# ProjectAir_Sch.net
KiCad netlist of a schematic drawn in Altium Designer
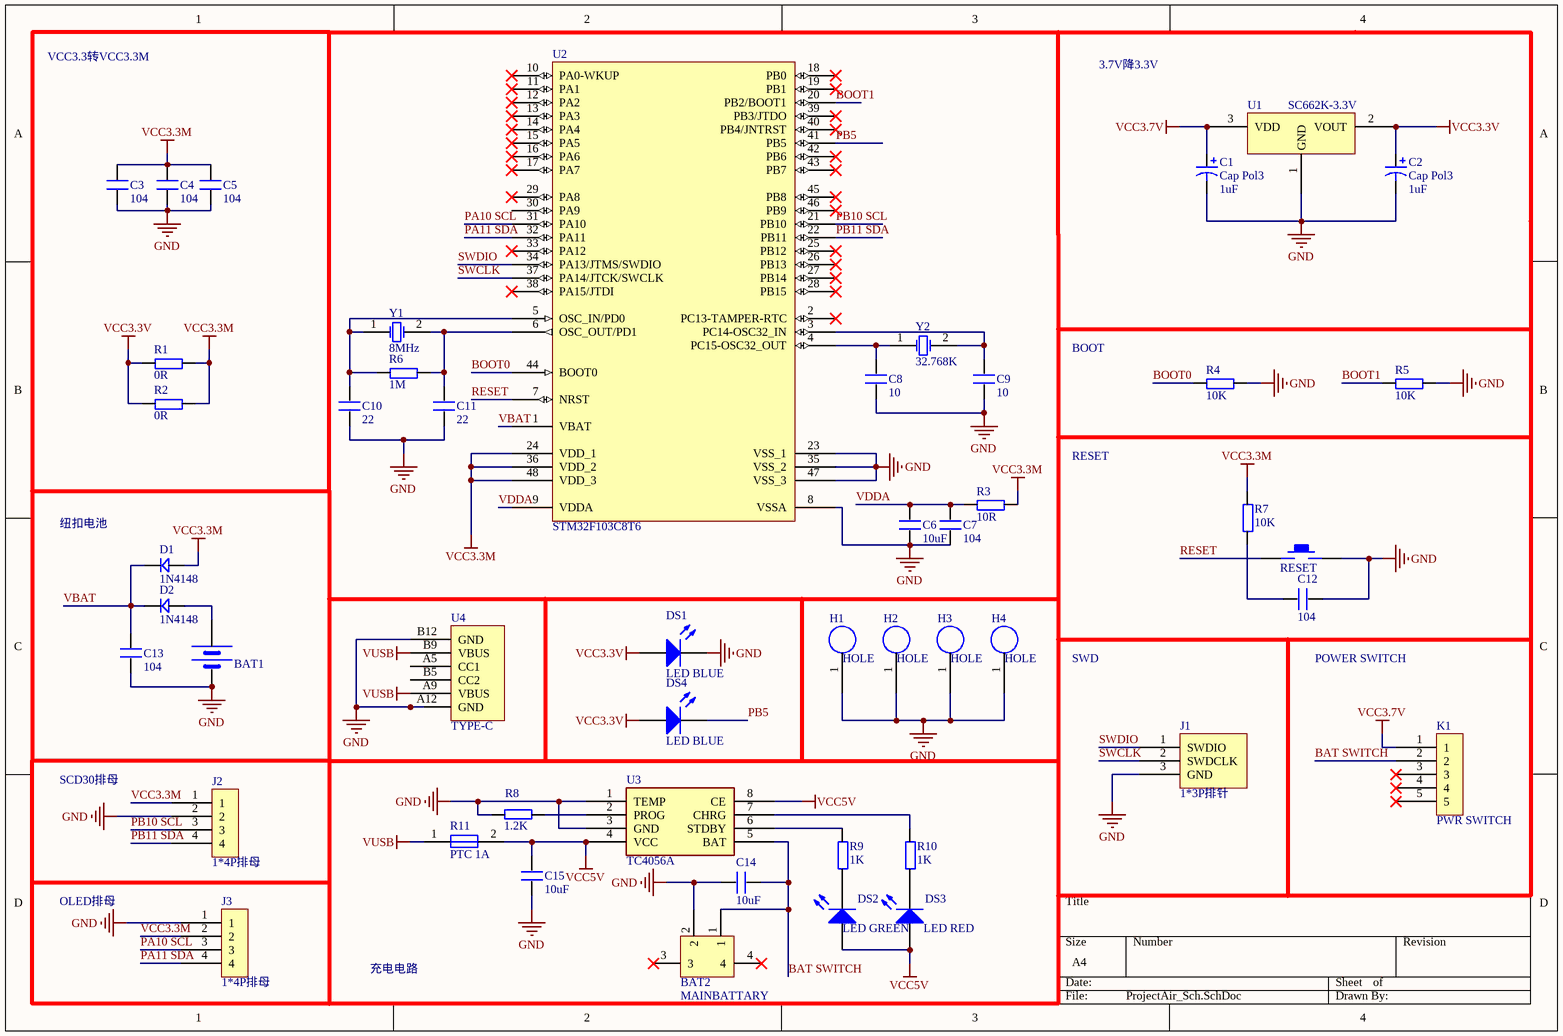
[diagram p0: ProjectAir_Sch.SchDoc]

(export (version "E")
  (design (tool "Eeschema 10.0.6"))
  (components
    (comp (ref "BAT1") (value "BATT") (footprint "BAT_RTC") (libsource (lib "EliteSTM32封装库") (part "BAT")))
    (comp (ref "BAT2")
      (value "MAINBATTARY")
      (footprint "MAINBAT")
      (libsource (lib "ProjectAir_SchLib") (part "MAINBAT"))
    )
    (comp (ref "C1")
      (value "Cap Pol3")
      (footprint "C Pol")
      (description "Polarized Capacitor (Surface Mount)")
      (fields (field (name "ALTIUM_VALUE") "1uF") (field (name "PUBLISHER") "Altium Limited"))
      (libsource (lib "Miscellaneous Devices") (part "Cap Pol3"))
    )
    (comp (ref "C2")
      (value "Cap Pol3")
      (footprint "C Pol")
      (description "Polarized Capacitor (Surface Mount)")
      (fields (field (name "ALTIUM_VALUE") "1uF") (field (name "PUBLISHER") "Altium Limited"))
      (libsource (lib "Miscellaneous Devices") (part "Cap Pol3"))
    )
    (comp (ref "C3") (value "104") (footprint "0805") (libsource (lib "EliteSTM32封装库") (part "C")))
    (comp (ref "C4") (value "104") (footprint "0805") (libsource (lib "EliteSTM32封装库") (part "C")))
    (comp (ref "C5") (value "104") (footprint "0805") (libsource (lib "EliteSTM32封装库") (part "C")))
    (comp (ref "C6") (value "10uF") (footprint "0805") (libsource (lib "EliteSTM32封装库") (part "C")))
    (comp (ref "C7") (value "104") (footprint "0805") (libsource (lib "EliteSTM32封装库") (part "C")))
    (comp (ref "C8") (value "10") (footprint "0805") (libsource (lib "EliteSTM32封装库") (part "C")))
    (comp (ref "C9") (value "10") (footprint "0805") (libsource (lib "EliteSTM32封装库") (part "C")))
    (comp (ref "C10") (value "22") (footprint "0805") (libsource (lib "EliteSTM32封装库") (part "C")))
    (comp (ref "C11") (value "22") (footprint "0805") (libsource (lib "EliteSTM32封装库") (part "C")))
    (comp (ref "C12") (value "104") (footprint "0805") (libsource (lib "EliteSTM32封装库") (part "C")))
    (comp (ref "C13") (value "104") (footprint "0805") (libsource (lib "EliteSTM32封装库") (part "C")))
    (comp (ref "C14") (value "10uF") (footprint "0805") (libsource (lib "EliteSTM32封装库") (part "C_2")))
    (comp (ref "C15") (value "10uF") (footprint "0805") (libsource (lib "EliteSTM32封装库") (part "C_2")))
    (comp (ref "D1") (value "1N4148") (footprint "SOD-123") (libsource (lib "EliteSTM32封装库") (part "D")))
    (comp (ref "D2") (value "1N4148") (footprint "SOD-123") (libsource (lib "EliteSTM32封装库") (part "D")))
    (comp (ref "DS1")
      (value "LED BLUE")
      (footprint "0805D")
      (description "Typical RED, GREEN, YELLOW, AMBER GaAs LED")
      (fields (field (name "PUBLISHER") "Altium Limited"))
      (libsource (lib "EliteSTM32封装库") (part "LED2"))
    )
    (comp (ref "DS2")
      (value "LED GREEN")
      (footprint "0805D")
      (description "Typical RED, GREEN, YELLOW, AMBER GaAs LED")
      (fields (field (name "PUBLISHER") "Altium Limited"))
      (libsource (lib "EliteSTM32封装库") (part "LED2"))
    )
    (comp (ref "DS3")
      (value "LED RED")
      (footprint "0805D")
      (description "Typical RED, GREEN, YELLOW, AMBER GaAs LED")
      (fields (field (name "PUBLISHER") "Altium Limited"))
      (libsource (lib "EliteSTM32封装库") (part "LED2"))
    )
    (comp (ref "DS4")
      (value "LED BLUE")
      (footprint "0805D")
      (description "Typical RED, GREEN, YELLOW, AMBER GaAs LED")
      (fields (field (name "PUBLISHER") "Altium Limited"))
      (libsource (lib "EliteSTM32封装库") (part "LED2"))
    )
    (comp (ref "H1")
      (value "HOLE")
      (footprint "M2孔")
      (description "M2孔")
      (libsource (lib "altium-import") (part "root_1_M2孔_"))
    )
    (comp (ref "H2")
      (value "HOLE")
      (footprint "M2孔")
      (description "M2孔")
      (libsource (lib "altium-import") (part "root_1_M2孔_"))
    )
    (comp (ref "H3")
      (value "HOLE")
      (footprint "M2孔")
      (description "M2孔")
      (libsource (lib "altium-import") (part "root_1_M2孔_"))
    )
    (comp (ref "H4")
      (value "HOLE")
      (footprint "M2孔")
      (description "M2孔")
      (libsource (lib "altium-import") (part "root_1_M2孔_"))
    )
    (comp (ref "J1")
      (value "1*3P排针")
      (footprint "1*3Pin")
      (libsource (lib "altium-import") (part "root_0_1*3P排针_"))
    )
    (comp (ref "J2")
      (value "1*4P排母")
      (footprint "1*4Pin")
      (description "排母")
      (libsource (lib "ProjectAir_SchLib") (part "1*4P排母"))
    )
    (comp (ref "J3")
      (value "1*4P排母")
      (footprint "1*4Pin")
      (description "排母")
      (libsource (lib "ProjectAir_SchLib") (part "1*4P排母"))
    )
    (comp (ref "K1")
      (value "PWR SWITCH")
      (footprint "PWR SWITCH")
      (libsource (lib "altium-import") (part "root_0_PWR SWITCH_"))
    )
    (comp (ref "R1") (value "0R") (footprint "0805R") (libsource (lib "EliteSTM32封装库") (part "R")))
    (comp (ref "R2") (value "0R") (footprint "0805R") (libsource (lib "EliteSTM32封装库") (part "R")))
    (comp (ref "R3") (value "10R") (footprint "0805R") (libsource (lib "EliteSTM32封装库") (part "R")))
    (comp (ref "R4") (value "10K") (footprint "0805R") (libsource (lib "EliteSTM32封装库") (part "R")))
    (comp (ref "R5") (value "10K") (footprint "0805R") (libsource (lib "EliteSTM32封装库") (part "R")))
    (comp (ref "R6") (value "1M") (footprint "0805R") (libsource (lib "EliteSTM32封装库") (part "R")))
    (comp (ref "R7") (value "10K") (footprint "0805R") (libsource (lib "EliteSTM32封装库") (part "R")))
    (comp (ref "R8") (value "1.2K") (footprint "0805R") (libsource (lib "EliteSTM32封装库") (part "R_1")))
    (comp (ref "R9") (value "1K") (footprint "0805R") (libsource (lib "EliteSTM32封装库") (part "R_1")))
    (comp (ref "R10") (value "1K") (footprint "0805R") (libsource (lib "EliteSTM32封装库") (part "R_1")))
    (comp (ref "R11")
      (value "PTC 1A")
      (footprint "PTC")
      (libsource (lib "altium-import") (part "root_0_PTC保险_"))
    )
    (comp (ref "RESET") (value "KEY_M") (footprint "SMD") (libsource (lib "EliteSTM32封装库") (part "KEY_M")))
    (comp (ref "U1")
      (value "SC662K-3.3V")
      (footprint "SOT23-3")
      (description "SCK662K-3.3V")
      (libsource (lib "ProjectAir_SchLib") (part "SC662K-3.3V"))
    )
    (comp (ref "U2")
      (value "STM32F103C8T6")
      (footprint "STM32F103C8T6")
      (description "STM32 ARM-based 32-bit MCU with 64 Kbytes Flash, 48-pin LQFP, Industrial Temperature")
      (fields (field (name "PUBLISHER") "Altium Limited"))
      (libsource (lib "ST Microcontroller 32-Bit STM32") (part "STM32F103C8T6"))
    )
    (comp (ref "U3")
      (value "TC4056A")
      (footprint "ESOP-8")
      (description "充电芯片")
      (libsource (lib "ProjectAir_SchLib") (part "TC4056A"))
    )
    (comp (ref "U4")
      (value "TYPE-C")
      (footprint "TYPE-C")
      (libsource (lib "ProjectAir_SchLib") (part "TYPE-C"))
    )
    (comp (ref "Y1")
      (value "8MHz")
      (footprint "SMD-5032_2P")
      (description "Crystal Oscillator")
      (fields (field (name "PUBLISHER") "Altium Limited"))
      (libsource (lib "EliteSTM32封装库") (part "XTAL"))
    )
    (comp (ref "Y2")
      (value "32.768K")
      (footprint "SMD_1610")
      (description "Crystal Oscillator")
      (fields (field (name "PUBLISHER") "Altium Limited"))
      (libsource (lib "EliteSTM32封装库") (part "XTAL_1"))
    )
  )
  (nets
    (net (code "1") (name "/BAT SWITCH") (class "Default")
      (node (ref "BAT2") (pin "1") (pinfunction "1_1") (pintype "passive"))
      (node (ref "C14") (pin "2") (pintype "passive"))
      (node (ref "K1") (pin "2") (pinfunction "2_2") (pintype "passive"))
      (node (ref "U3") (pin "5") (pinfunction "BAT_5") (pintype "passive"))
    )
    (net (code "2") (name "/BOOT0") (class "Default")
      (node (ref "R4") (pin "1") (pintype "passive"))
      (node (ref "U2") (pin "44") (pinfunction "BOOT0_44") (pintype "input"))
    )
    (net (code "3") (name "/BOOT1") (class "Default")
      (node (ref "R5") (pin "1") (pintype "passive"))
      (node (ref "U2") (pin "20") (pinfunction "PB2/BOOT1_20") (pintype "bidirectional"))
    )
    (net (code "4") (name "/PA10 SCL") (class "Default")
      (node (ref "J3") (pin "3") (pinfunction "3_3") (pintype "passive"))
      (node (ref "U2") (pin "31") (pinfunction "PA10_31") (pintype "bidirectional"))
    )
    (net (code "5") (name "/PA11 SDA") (class "Default")
      (node (ref "J3") (pin "4") (pinfunction "4_4") (pintype "passive"))
      (node (ref "U2") (pin "32") (pinfunction "PA11_32") (pintype "bidirectional"))
    )
    (net (code "6") (name "/PB5") (class "Default")
      (node (ref "DS4") (pin "2") (pinfunction "K_2") (pintype "passive"))
      (node (ref "U2") (pin "41") (pinfunction "PB5_41") (pintype "bidirectional"))
    )
    (net (code "7") (name "/PB10 SCL") (class "Default")
      (node (ref "J2") (pin "3") (pinfunction "3_3") (pintype "passive"))
      (node (ref "U2") (pin "21") (pinfunction "PB10_21") (pintype "bidirectional"))
    )
    (net (code "8") (name "/PB11 SDA") (class "Default")
      (node (ref "J2") (pin "4") (pinfunction "4_4") (pintype "passive"))
      (node (ref "U2") (pin "22") (pinfunction "PB11_22") (pintype "bidirectional"))
    )
    (net (code "9") (name "/RESET") (class "Default")
      (node (ref "RESET") (pin "1") (pinfunction "1_1") (pintype "passive"))
      (node (ref "U2") (pin "7") (pinfunction "NRST_7") (pintype "bidirectional"))
    )
    (net (code "10") (name "/SWCLK") (class "Default")
      (node (ref "J1") (pin "2") (pinfunction "SWDCLK_2") (pintype "passive"))
      (node (ref "U2") (pin "37") (pinfunction "PA14/JTCK/SWCLK_37") (pintype "bidirectional"))
    )
    (net (code "11") (name "/SWDIO") (class "Default")
      (node (ref "J1") (pin "1") (pinfunction "SWDIO_1") (pintype "passive"))
      (node (ref "U2") (pin "34") (pinfunction "PA13/JTMS/SWDIO_34") (pintype "bidirectional"))
    )
    (net (code "12") (name "/VBAT") (class "Default")
      (node (ref "C13") (pin "2") (pintype "passive"))
      (node (ref "D1") (pin "2") (pintype "passive"))
      (node (ref "D2") (pin "2") (pintype "passive"))
      (node (ref "U2") (pin "1") (pinfunction "VBAT_1") (pintype "power_in"))
    )
    (net (code "13") (name "/VDDA") (class "Default")
      (node (ref "C6") (pin "2") (pintype "passive"))
      (node (ref "C7") (pin "2") (pintype "passive"))
      (node (ref "R3") (pin "1") (pintype "passive"))
      (node (ref "U2") (pin "9") (pinfunction "VDDA_9") (pintype "power_in"))
    )
    (net (code "14") (name "GND") (class "Default")
      (node (ref "BAT1") (pin "2") (pinfunction "GND_2") (pintype "passive"))
      (node (ref "BAT2") (pin "2") (pinfunction "2_2") (pintype "passive"))
      (node (ref "C1") (pin "2") (pinfunction "2_2") (pintype "passive"))
      (node (ref "C10") (pin "1") (pintype "passive"))
      (node (ref "C11") (pin "1") (pintype "passive"))
      (node (ref "C12") (pin "2") (pintype "passive"))
      (node (ref "C13") (pin "1") (pintype "passive"))
      (node (ref "C14") (pin "1") (pintype "passive"))
      (node (ref "C15") (pin "1") (pintype "passive"))
      (node (ref "C2") (pin "2") (pinfunction "2_2") (pintype "passive"))
      (node (ref "C3") (pin "1") (pintype "passive"))
      (node (ref "C4") (pin "1") (pintype "passive"))
      (node (ref "C5") (pin "1") (pintype "passive"))
      (node (ref "C6") (pin "1") (pintype "passive"))
      (node (ref "C7") (pin "1") (pintype "passive"))
      (node (ref "C8") (pin "1") (pintype "passive"))
      (node (ref "C9") (pin "1") (pintype "passive"))
      (node (ref "DS1") (pin "2") (pinfunction "K_2") (pintype "passive"))
      (node (ref "H1") (pin "1") (pinfunction "GND_1") (pintype "passive"))
      (node (ref "H2") (pin "1") (pinfunction "GND_1") (pintype "passive"))
      (node (ref "H3") (pin "1") (pinfunction "GND_1") (pintype "passive"))
      (node (ref "H4") (pin "1") (pinfunction "GND_1") (pintype "passive"))
      (node (ref "J1") (pin "3") (pinfunction "GND_3") (pintype "passive"))
      (node (ref "J2") (pin "2") (pinfunction "2_2") (pintype "passive"))
      (node (ref "J3") (pin "1") (pinfunction "1_1") (pintype "passive"))
      (node (ref "R4") (pin "2") (pintype "passive"))
      (node (ref "R5") (pin "2") (pintype "passive"))
      (node (ref "R8") (pin "2") (pintype "passive"))
      (node (ref "RESET") (pin "2") (pinfunction "2_2") (pintype "passive"))
      (node (ref "U1") (pin "1") (pinfunction "GND_1") (pintype "passive"))
      (node (ref "U2") (pin "23") (pinfunction "VSS_1_23") (pintype "power_in"))
      (node (ref "U2") (pin "35") (pinfunction "VSS_2_35") (pintype "power_in"))
      (node (ref "U2") (pin "47") (pinfunction "VSS_3_47") (pintype "power_in"))
      (node (ref "U2") (pin "8") (pinfunction "VSSA_8") (pintype "power_in"))
      (node (ref "U3") (pin "1") (pinfunction "TEMP_1") (pintype "passive"))
      (node (ref "U3") (pin "3") (pinfunction "GND_3") (pintype "passive"))
      (node (ref "U4") (pin "A12") (pinfunction "GND_A12") (pintype "passive"))
      (node (ref "U4") (pin "B12") (pinfunction "GND_B12") (pintype "passive"))
    )
    (net (code "15") (name "Net-(BAT1-VCC)") (class "Default")
      (node (ref "BAT1") (pin "1") (pinfunction "VCC_1") (pintype "passive"))
      (node (ref "D2") (pin "1") (pintype "passive"))
    )
    (net (code "16") (name "Net-(C12-Pad1)") (class "Default")
      (node (ref "C12") (pin "1") (pintype "passive"))
      (node (ref "R7") (pin "1") (pintype "passive"))
    )
    (net (code "17") (name "Net-(DS2-K)") (class "Default")
      (node (ref "DS2") (pin "2") (pinfunction "K_2") (pintype "passive"))
      (node (ref "R9") (pin "1") (pintype "passive"))
    )
    (net (code "18") (name "Net-(DS3-K)") (class "Default")
      (node (ref "DS3") (pin "2") (pinfunction "K_2") (pintype "passive"))
      (node (ref "R10") (pin "1") (pintype "passive"))
    )
    (net (code "19") (name "Net-(U2-OSC_IN{slash}PD0)") (class "Default")
      (node (ref "C10") (pin "2") (pintype "passive"))
      (node (ref "R6") (pin "1") (pintype "passive"))
      (node (ref "U2") (pin "5") (pinfunction "OSC_IN/PD0_5") (pintype "input"))
      (node (ref "Y1") (pin "1") (pinfunction "OSC1_1") (pintype "passive"))
    )
    (net (code "20") (name "Net-(U2-OSC_OUT{slash}PD1)") (class "Default")
      (node (ref "C11") (pin "2") (pintype "passive"))
      (node (ref "R6") (pin "2") (pintype "passive"))
      (node (ref "U2") (pin "6") (pinfunction "OSC_OUT/PD1_6") (pintype "output"))
      (node (ref "Y1") (pin "2") (pinfunction "OSC2_2") (pintype "passive"))
    )
    (net (code "21") (name "Net-(U2-PC14-OSC32_IN)") (class "Default")
      (node (ref "C9") (pin "2") (pintype "passive"))
      (node (ref "U2") (pin "3") (pinfunction "PC14-OSC32_IN_3") (pintype "bidirectional"))
      (node (ref "Y2") (pin "2") (pinfunction "OSC2_2") (pintype "passive"))
    )
    (net (code "22") (name "Net-(U2-PC15-OSC32_OUT)") (class "Default")
      (node (ref "C8") (pin "2") (pintype "passive"))
      (node (ref "U2") (pin "4") (pinfunction "PC15-OSC32_OUT_4") (pintype "bidirectional"))
      (node (ref "Y2") (pin "1") (pinfunction "OSC1_1") (pintype "passive"))
    )
    (net (code "23") (name "Net-(U3-CHRG)") (class "Default")
      (node (ref "R10") (pin "2") (pintype "passive"))
      (node (ref "U3") (pin "7") (pinfunction "CHRG_7") (pintype "passive"))
    )
    (net (code "24") (name "Net-(U3-PROG)") (class "Default")
      (node (ref "R8") (pin "1") (pintype "passive"))
      (node (ref "U3") (pin "2") (pinfunction "PROG_2") (pintype "passive"))
    )
    (net (code "25") (name "Net-(U3-STDBY)") (class "Default")
      (node (ref "R9") (pin "2") (pintype "passive"))
      (node (ref "U3") (pin "6") (pinfunction "STDBY_6") (pintype "passive"))
    )
    (net (code "26") (name "VCC3.3M") (class "Default")
      (node (ref "C3") (pin "2") (pintype "passive"))
      (node (ref "C4") (pin "2") (pintype "passive"))
      (node (ref "C5") (pin "2") (pintype "passive"))
      (node (ref "D1") (pin "1") (pintype "passive"))
      (node (ref "J2") (pin "1") (pinfunction "1_1") (pintype "passive"))
      (node (ref "J3") (pin "2") (pinfunction "2_2") (pintype "passive"))
      (node (ref "R1") (pin "2") (pintype "passive"))
      (node (ref "R2") (pin "2") (pintype "passive"))
      (node (ref "R3") (pin "2") (pintype "passive"))
      (node (ref "R7") (pin "2") (pintype "passive"))
      (node (ref "U2") (pin "24") (pinfunction "VDD_1_24") (pintype "power_in"))
      (node (ref "U2") (pin "36") (pinfunction "VDD_2_36") (pintype "power_in"))
      (node (ref "U2") (pin "48") (pinfunction "VDD_3_48") (pintype "power_in"))
    )
    (net (code "27") (name "VCC3.3V") (class "Default")
      (node (ref "C2") (pin "1") (pinfunction "1_1") (pintype "passive"))
      (node (ref "DS1") (pin "1") (pinfunction "A_1") (pintype "passive"))
      (node (ref "DS4") (pin "1") (pinfunction "A_1") (pintype "passive"))
      (node (ref "R1") (pin "1") (pintype "passive"))
      (node (ref "R2") (pin "1") (pintype "passive"))
      (node (ref "U1") (pin "2") (pinfunction "VOUT_2") (pintype "passive"))
    )
    (net (code "28") (name "VCC3.7V") (class "Default")
      (node (ref "C1") (pin "1") (pinfunction "1_1") (pintype "passive"))
      (node (ref "K1") (pin "1") (pinfunction "1_1") (pintype "passive"))
      (node (ref "U1") (pin "3") (pinfunction "VDD_3") (pintype "passive"))
    )
    (net (code "29") (name "VCC5V") (class "Default")
      (node (ref "C15") (pin "2") (pintype "passive"))
      (node (ref "DS2") (pin "1") (pinfunction "A_1") (pintype "passive"))
      (node (ref "DS3") (pin "1") (pinfunction "A_1") (pintype "passive"))
      (node (ref "R11") (pin "2") (pinfunction "2_2") (pintype "passive"))
      (node (ref "U3") (pin "4") (pinfunction "VCC_4") (pintype "passive"))
      (node (ref "U3") (pin "8") (pinfunction "CE_8") (pintype "passive"))
    )
    (net (code "30") (name "VUSB") (class "Default")
      (node (ref "R11") (pin "1") (pinfunction "1_1") (pintype "passive"))
      (node (ref "U4") (pin "A9") (pinfunction "VBUS_A9") (pintype "passive"))
      (node (ref "U4") (pin "B9") (pinfunction "VBUS_B9") (pintype "passive"))
    )
    (net (code "31") (name "unconnected-(BAT2-Pad3)") (class "Default")
      (node (ref "BAT2") (pin "3") (pinfunction "3_3") (pintype "passive+no_connect"))
    )
    (net (code "32") (name "unconnected-(BAT2-Pad4)") (class "Default")
      (node (ref "BAT2") (pin "4") (pinfunction "4_4") (pintype "passive+no_connect"))
    )
    (net (code "33") (name "unconnected-(K1-Pad3)") (class "Default")
      (node (ref "K1") (pin "3") (pinfunction "3_3") (pintype "passive+no_connect"))
    )
    (net (code "34") (name "unconnected-(K1-Pad4)") (class "Default")
      (node (ref "K1") (pin "4") (pinfunction "4_4") (pintype "passive+no_connect"))
    )
    (net (code "35") (name "unconnected-(K1-Pad5)") (class "Default")
      (node (ref "K1") (pin "5") (pinfunction "5_5") (pintype "passive+no_connect"))
    )
    (net (code "36") (name "unconnected-(U2-PA0-WKUP-Pad10)") (class "Default")
      (node (ref "U2") (pin "10") (pinfunction "PA0-WKUP_10") (pintype "bidirectional+no_connect"))
    )
    (net (code "37") (name "unconnected-(U2-PA1-Pad11)") (class "Default")
      (node (ref "U2") (pin "11") (pinfunction "PA1_11") (pintype "bidirectional+no_connect"))
    )
    (net (code "38") (name "unconnected-(U2-PA2-Pad12)") (class "Default")
      (node (ref "U2") (pin "12") (pinfunction "PA2_12") (pintype "bidirectional+no_connect"))
    )
    (net (code "39") (name "unconnected-(U2-PA3-Pad13)") (class "Default")
      (node (ref "U2") (pin "13") (pinfunction "PA3_13") (pintype "bidirectional+no_connect"))
    )
    (net (code "40") (name "unconnected-(U2-PA4-Pad14)") (class "Default")
      (node (ref "U2") (pin "14") (pinfunction "PA4_14") (pintype "bidirectional+no_connect"))
    )
    (net (code "41") (name "unconnected-(U2-PA5-Pad15)") (class "Default")
      (node (ref "U2") (pin "15") (pinfunction "PA5_15") (pintype "bidirectional+no_connect"))
    )
    (net (code "42") (name "unconnected-(U2-PA6-Pad16)") (class "Default")
      (node (ref "U2") (pin "16") (pinfunction "PA6_16") (pintype "bidirectional+no_connect"))
    )
    (net (code "43") (name "unconnected-(U2-PA7-Pad17)") (class "Default")
      (node (ref "U2") (pin "17") (pinfunction "PA7_17") (pintype "bidirectional+no_connect"))
    )
    (net (code "44") (name "unconnected-(U2-PA8-Pad29)") (class "Default")
      (node (ref "U2") (pin "29") (pinfunction "PA8_29") (pintype "bidirectional+no_connect"))
    )
    (net (code "45") (name "unconnected-(U2-PA9-Pad30)") (class "Default")
      (node (ref "U2") (pin "30") (pinfunction "PA9_30") (pintype "bidirectional"))
    )
    (net (code "46") (name "unconnected-(U2-PA12-Pad33)") (class "Default")
      (node (ref "U2") (pin "33") (pinfunction "PA12_33") (pintype "bidirectional+no_connect"))
    )
    (net (code "47") (name "unconnected-(U2-PA15{slash}JTDI-Pad38)") (class "Default")
      (node (ref "U2") (pin "38") (pinfunction "PA15/JTDI_38") (pintype "bidirectional+no_connect"))
    )
    (net (code "48") (name "unconnected-(U2-PB0-Pad18)") (class "Default")
      (node (ref "U2") (pin "18") (pinfunction "PB0_18") (pintype "bidirectional+no_connect"))
    )
    (net (code "49") (name "unconnected-(U2-PB1-Pad19)") (class "Default")
      (node (ref "U2") (pin "19") (pinfunction "PB1_19") (pintype "bidirectional+no_connect"))
    )
    (net (code "50") (name "unconnected-(U2-PB3{slash}JTDO-Pad39)") (class "Default")
      (node (ref "U2") (pin "39") (pinfunction "PB3/JTDO_39") (pintype "bidirectional+no_connect"))
    )
    (net (code "51") (name "unconnected-(U2-PB4{slash}JNTRST-Pad40)") (class "Default")
      (node (ref "U2") (pin "40") (pinfunction "PB4/JNTRST_40") (pintype "bidirectional+no_connect"))
    )
    (net (code "52") (name "unconnected-(U2-PB6-Pad42)") (class "Default")
      (node (ref "U2") (pin "42") (pinfunction "PB6_42") (pintype "bidirectional+no_connect"))
    )
    (net (code "53") (name "unconnected-(U2-PB7-Pad43)") (class "Default")
      (node (ref "U2") (pin "43") (pinfunction "PB7_43") (pintype "bidirectional+no_connect"))
    )
    (net (code "54") (name "unconnected-(U2-PB8-Pad45)") (class "Default")
      (node (ref "U2") (pin "45") (pinfunction "PB8_45") (pintype "bidirectional+no_connect"))
    )
    (net (code "55") (name "unconnected-(U2-PB9-Pad46)") (class "Default")
      (node (ref "U2") (pin "46") (pinfunction "PB9_46") (pintype "bidirectional+no_connect"))
    )
    (net (code "56") (name "unconnected-(U2-PB12-Pad25)") (class "Default")
      (node (ref "U2") (pin "25") (pinfunction "PB12_25") (pintype "bidirectional+no_connect"))
    )
    (net (code "57") (name "unconnected-(U2-PB13-Pad26)") (class "Default")
      (node (ref "U2") (pin "26") (pinfunction "PB13_26") (pintype "bidirectional+no_connect"))
    )
    (net (code "58") (name "unconnected-(U2-PB14-Pad27)") (class "Default")
      (node (ref "U2") (pin "27") (pinfunction "PB14_27") (pintype "bidirectional+no_connect"))
    )
    (net (code "59") (name "unconnected-(U2-PB15-Pad28)") (class "Default")
      (node (ref "U2") (pin "28") (pinfunction "PB15_28") (pintype "bidirectional+no_connect"))
    )
    (net (code "60") (name "unconnected-(U2-PC13-TAMPER-RTC-Pad2)") (class "Default")
      (node (ref "U2") (pin "2") (pinfunction "PC13-TAMPER-RTC_2") (pintype "bidirectional+no_connect"))
    )
    (net (code "61") (name "unconnected-(U4-CC1-PadA5)") (class "Default")
      (node (ref "U4") (pin "A5") (pinfunction "CC1_A5") (pintype "passive"))
    )
    (net (code "62") (name "unconnected-(U4-CC2-PadB5)") (class "Default")
      (node (ref "U4") (pin "B5") (pinfunction "CC2_B5") (pintype "passive"))
    )
  )
)
